# PAGE2.net
KiCad netlist of a schematic drawn in Altium Designer
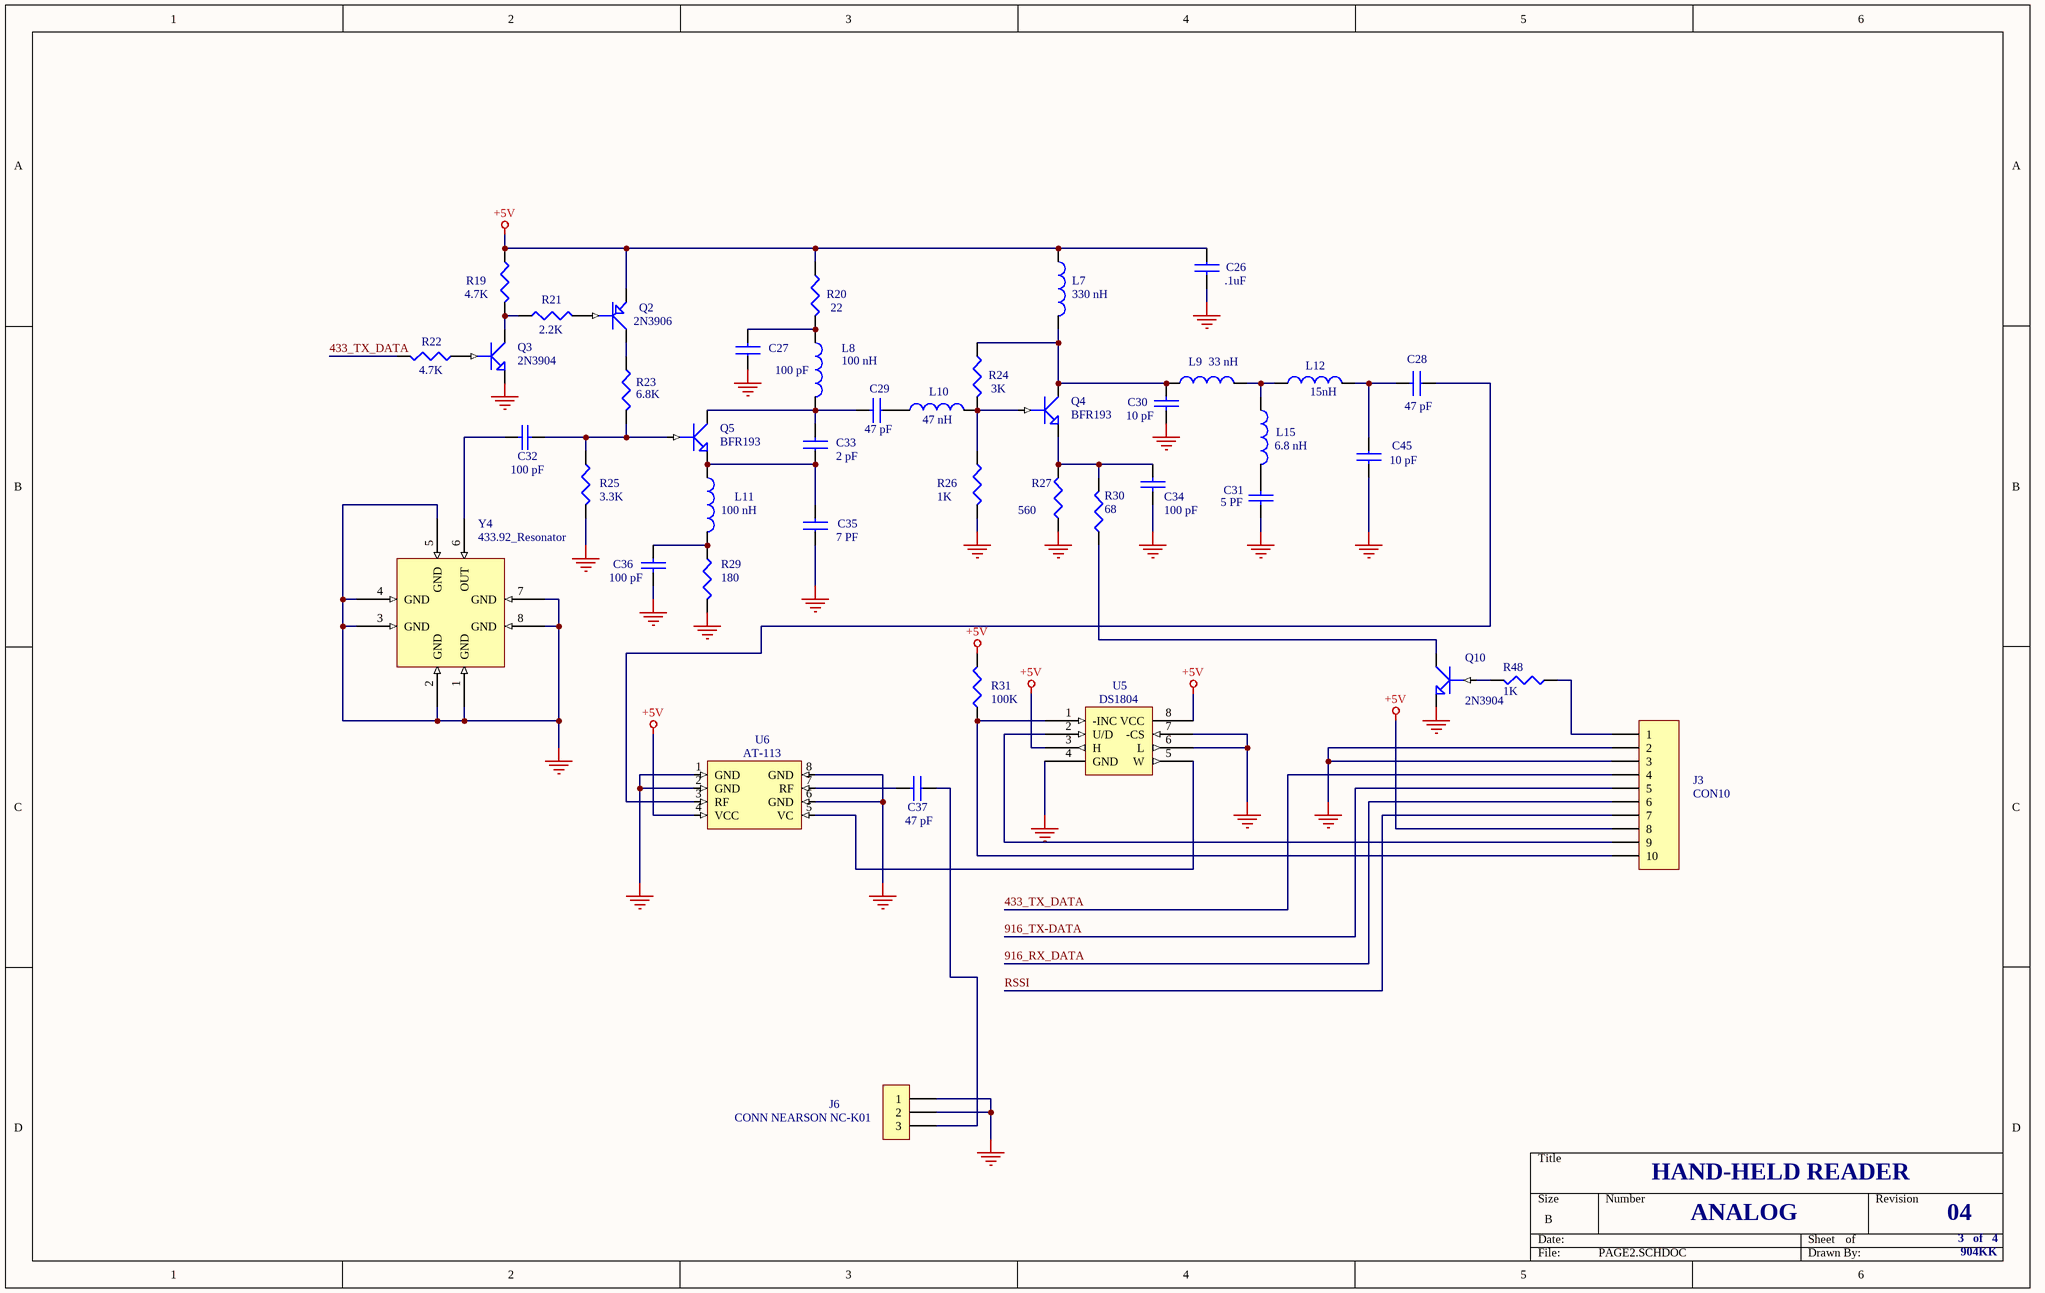
[diagram p0: PAGE2.SCHDOC]

(export (version "E")
  (design (tool "Eeschema 10.0.6"))
  (components
    (comp (ref "C26") (value ".1uF") (footprint "0603") (libsource (lib "*") (part "CAP_NP")))
    (comp (ref "C27") (value "100 pF") (footprint "0603") (libsource (lib "*") (part "CAP_NP")))
    (comp (ref "C28") (value "47 pF") (footprint "0603") (libsource (lib "*") (part "CAP_NP")))
    (comp (ref "C29") (value "47 pF") (footprint "0603") (libsource (lib "*") (part "CAP_NP")))
    (comp (ref "C30")
      (value "10 pF")
      (footprint "0603")
      (description "Capacitor")
      (libsource (lib "*") (part "CAP"))
    )
    (comp (ref "C31")
      (value "5 PF")
      (footprint "0603")
      (description "Capacitor")
      (libsource (lib "*") (part "CAP"))
    )
    (comp (ref "C32")
      (value "100 pF")
      (footprint "0603")
      (description "Capacitor")
      (libsource (lib "*") (part "CAP"))
    )
    (comp (ref "C33") (value "2 pF") (footprint "0603") (libsource (lib "*") (part "CAP_NP")))
    (comp (ref "C34")
      (value "100 pF")
      (footprint "0603")
      (description "Capacitor")
      (libsource (lib "*") (part "CAP"))
    )
    (comp (ref "C35") (value "7 PF") (footprint "0603") (libsource (lib "*") (part "CAP_NP")))
    (comp (ref "C36")
      (value "100 pF")
      (footprint "0603")
      (description "Capacitor")
      (libsource (lib "*") (part "CAP"))
    )
    (comp (ref "C37") (value "47 pF") (footprint "0603") (libsource (lib "*") (part "CAP_NP")))
    (comp (ref "C45") (value "10 pF") (footprint "0603") (libsource (lib "*") (part "CAP_NP")))
    (comp (ref "J3")
      (value "CON10")
      (footprint "1X10 HEADER SPECIAL")
      (description "Connector")
      (libsource (lib "*") (part "CON10"))
    )
    (comp (ref "J6")
      (value "CONN NEARSON NC-K01")
      (footprint "CONN NEARSON NC-K01")
      (description "Connector")
      (libsource (lib "*") (part "CON3"))
    )
    (comp (ref "L7") (value "330 nH") (footprint "0805") (libsource (lib "*") (part "INDUCTOR")))
    (comp (ref "L8") (value "100 nH") (footprint "0603") (libsource (lib "*") (part "INDUCTOR")))
    (comp (ref "L9") (value "33 nH") (footprint "0603") (libsource (lib "*") (part "INDUCTOR")))
    (comp (ref "L10") (value "47 nH") (footprint "0603") (libsource (lib "*") (part "INDUCTOR")))
    (comp (ref "L11") (value "100 nH") (footprint "0603") (libsource (lib "*") (part "INDUCTOR")))
    (comp (ref "L12") (value "15nH") (footprint "0603") (libsource (lib "*") (part "INDUCTOR")))
    (comp (ref "L15") (value "6.8 nH") (footprint "0603") (libsource (lib "*") (part "INDUCTOR")))
    (comp (ref "Q2")
      (value "2N3906")
      (footprint "SOT23 TRANS")
      (description "PNP Transistor")
      (libsource (lib "*") (part "PNP1"))
    )
    (comp (ref "Q3")
      (value "2N3904")
      (footprint "SOT23 TRANS")
      (description "NPN Transistor")
      (libsource (lib "*") (part "NPN1"))
    )
    (comp (ref "Q4")
      (value "BFR193")
      (footprint "SOT23 TRANS")
      (description "NPN Transistor")
      (libsource (lib "*") (part "NPN1"))
    )
    (comp (ref "Q5")
      (value "BFR193")
      (footprint "SOT23 TRANS")
      (description "NPN Transistor")
      (libsource (lib "*") (part "NPN1"))
    )
    (comp (ref "Q10")
      (value "2N3904")
      (footprint "SOT23 TRANS")
      (description "NPN Transistor")
      (libsource (lib "*") (part "NPN1"))
    )
    (comp (ref "R19") (value "4.7K") (footprint "0603") (libsource (lib "*") (part "RESISTOR")))
    (comp (ref "R20") (value "22") (footprint "0603") (libsource (lib "*") (part "RESISTOR")))
    (comp (ref "R21") (value "2.2K") (footprint "0603") (libsource (lib "*") (part "RESISTOR")))
    (comp (ref "R22") (value "4.7K") (footprint "0603") (libsource (lib "*") (part "RESISTOR")))
    (comp (ref "R23") (value "6.8K") (footprint "0603") (libsource (lib "*") (part "RESISTOR")))
    (comp (ref "R24") (value "3K") (footprint "0603") (libsource (lib "*") (part "RESISTOR")))
    (comp (ref "R25") (value "3.3K") (footprint "0603") (libsource (lib "*") (part "RESISTOR")))
    (comp (ref "R26") (value "1K") (footprint "0603") (libsource (lib "*") (part "RESISTOR")))
    (comp (ref "R27") (value "560") (footprint "0603") (libsource (lib "*") (part "RESISTOR")))
    (comp (ref "R29") (value "180") (footprint "0603") (libsource (lib "*") (part "RESISTOR")))
    (comp (ref "R30") (value "68") (footprint "0603") (libsource (lib "*") (part "RESISTOR")))
    (comp (ref "R31") (value "100K") (footprint "0603") (libsource (lib "*") (part "RESISTOR")))
    (comp (ref "R48") (value "1K") (footprint "0603") (libsource (lib "*") (part "RESISTOR")))
    (comp (ref "U5") (value "DS1804") (footprint "SO8 SMALL") (libsource (lib "*") (part "DS1804")))
    (comp (ref "U6") (value "AT-113") (footprint "SO8") (libsource (lib "*") (part "AT-113A")))
    (comp (ref "Y4")
      (value "433.92_Resonator")
      (footprint "RESONATOR")
      (libsource (lib "*") (part "RESONATOR"))
    )
  )
  (nets
    (net (code "1") (name "+5V") (class "Default")
      (node (ref "C26") (pin "1") (pinfunction "1_1") (pintype "passive"))
      (node (ref "J3") (pin "8") (pinfunction "8_8") (pintype "passive"))
      (node (ref "L7") (pin "1") (pinfunction "1_1") (pintype "passive"))
      (node (ref "Q2") (pin "E") (pinfunction "E_E") (pintype "passive"))
      (node (ref "R19") (pin "1") (pinfunction "1_1") (pintype "passive"))
      (node (ref "R20") (pin "1") (pinfunction "1_1") (pintype "passive"))
      (node (ref "R31") (pin "1") (pinfunction "1_1") (pintype "passive"))
      (node (ref "U5") (pin "3") (pinfunction "H_3") (pintype "output"))
      (node (ref "U5") (pin "8") (pinfunction "VCC_8") (pintype "power_in"))
      (node (ref "U6") (pin "4") (pinfunction "VCC_4") (pintype "input"))
    )
    (net (code "2") (name "/433_TX_DATA") (class "Default")
      (node (ref "J3") (pin "4") (pinfunction "4_4") (pintype "passive"))
      (node (ref "R22") (pin "2") (pinfunction "2_2") (pintype "passive"))
    )
    (net (code "3") (name "/916_RX_DATA") (class "Default")
      (node (ref "J3") (pin "6") (pinfunction "6_6") (pintype "passive"))
    )
    (net (code "4") (name "/916_TX-DATA") (class "Default")
      (node (ref "J3") (pin "5") (pinfunction "5_5") (pintype "passive"))
    )
    (net (code "5") (name "/RSSI") (class "Default")
      (node (ref "J3") (pin "7") (pinfunction "7_7") (pintype "passive"))
    )
    (net (code "6") (name "GND_SIGNAL") (class "Default")
      (node (ref "C26") (pin "2") (pinfunction "2_2") (pintype "passive"))
      (node (ref "C27") (pin "1") (pinfunction "1_1") (pintype "passive"))
      (node (ref "C30") (pin "2") (pinfunction "2_2") (pintype "passive"))
      (node (ref "C31") (pin "2") (pinfunction "2_2") (pintype "passive"))
      (node (ref "C34") (pin "2") (pinfunction "2_2") (pintype "passive"))
      (node (ref "C35") (pin "1") (pinfunction "1_1") (pintype "passive"))
      (node (ref "C36") (pin "2") (pinfunction "2_2") (pintype "passive"))
      (node (ref "C45") (pin "2") (pinfunction "2_2") (pintype "passive"))
      (node (ref "J3") (pin "2") (pinfunction "2_2") (pintype "passive"))
      (node (ref "J3") (pin "3") (pinfunction "3_3") (pintype "passive"))
      (node (ref "J6") (pin "1") (pinfunction "1_1") (pintype "passive"))
      (node (ref "J6") (pin "2") (pinfunction "2_2") (pintype "passive"))
      (node (ref "Q10") (pin "E") (pinfunction "E_E") (pintype "passive"))
      (node (ref "Q3") (pin "E") (pinfunction "E_E") (pintype "passive"))
      (node (ref "R25") (pin "2") (pinfunction "2_2") (pintype "passive"))
      (node (ref "R26") (pin "2") (pinfunction "2_2") (pintype "passive"))
      (node (ref "R27") (pin "2") (pinfunction "2_2") (pintype "passive"))
      (node (ref "R29") (pin "2") (pinfunction "2_2") (pintype "passive"))
      (node (ref "U5") (pin "4") (pinfunction "GND_4") (pintype "power_in"))
      (node (ref "U5") (pin "6") (pinfunction "L_6") (pintype "output"))
      (node (ref "U5") (pin "7") (pinfunction "-CS_7") (pintype "input"))
      (node (ref "U6") (pin "1") (pinfunction "GND_1") (pintype "input"))
      (node (ref "U6") (pin "2") (pinfunction "GND_2") (pintype "input"))
      (node (ref "U6") (pin "6") (pinfunction "GND_6") (pintype "input"))
      (node (ref "U6") (pin "8") (pinfunction "GND_8") (pintype "input"))
      (node (ref "Y4") (pin "1") (pinfunction "GND_1") (pintype "input"))
      (node (ref "Y4") (pin "2") (pinfunction "GND_2") (pintype "input"))
      (node (ref "Y4") (pin "3") (pinfunction "GND_3") (pintype "input"))
      (node (ref "Y4") (pin "4") (pinfunction "GND_4") (pintype "input"))
      (node (ref "Y4") (pin "5") (pinfunction "GND_5") (pintype "input"))
      (node (ref "Y4") (pin "7") (pinfunction "GND_7") (pintype "input"))
      (node (ref "Y4") (pin "8") (pinfunction "GND_8") (pintype "input"))
    )
    (net (code "7") (name "Net-(C27-Pad2)") (class "Default")
      (node (ref "C27") (pin "2") (pinfunction "2_2") (pintype "passive"))
      (node (ref "L8") (pin "1") (pinfunction "1_1") (pintype "passive"))
      (node (ref "R20") (pin "2") (pinfunction "2_2") (pintype "passive"))
    )
    (net (code "8") (name "Net-(C28-Pad1)") (class "Default")
      (node (ref "C28") (pin "1") (pinfunction "1_1") (pintype "passive"))
      (node (ref "U6") (pin "3") (pinfunction "RF_3") (pintype "input"))
    )
    (net (code "9") (name "Net-(C28-Pad2)") (class "Default")
      (node (ref "C28") (pin "2") (pinfunction "2_2") (pintype "passive"))
      (node (ref "C45") (pin "1") (pinfunction "1_1") (pintype "passive"))
      (node (ref "L12") (pin "2") (pinfunction "2_2") (pintype "passive"))
    )
    (net (code "10") (name "Net-(C29-Pad1)") (class "Default")
      (node (ref "C29") (pin "1") (pinfunction "1_1") (pintype "passive"))
      (node (ref "L10") (pin "1") (pinfunction "1_1") (pintype "passive"))
    )
    (net (code "11") (name "Net-(C29-Pad2)") (class "Default")
      (node (ref "C29") (pin "2") (pinfunction "2_2") (pintype "passive"))
      (node (ref "C33") (pin "2") (pinfunction "2_2") (pintype "passive"))
      (node (ref "L8") (pin "2") (pinfunction "2_2") (pintype "passive"))
      (node (ref "Q5") (pin "C") (pinfunction "C_C") (pintype "passive"))
    )
    (net (code "12") (name "Net-(C30-Pad1)") (class "Default")
      (node (ref "C30") (pin "1") (pinfunction "1_1") (pintype "passive"))
      (node (ref "L7") (pin "2") (pinfunction "2_2") (pintype "passive"))
      (node (ref "L9") (pin "1") (pinfunction "1_1") (pintype "passive"))
      (node (ref "Q4") (pin "C") (pinfunction "C_C") (pintype "passive"))
      (node (ref "R24") (pin "1") (pinfunction "1_1") (pintype "passive"))
    )
    (net (code "13") (name "Net-(C31-Pad1)") (class "Default")
      (node (ref "C31") (pin "1") (pinfunction "1_1") (pintype "passive"))
      (node (ref "L15") (pin "2") (pinfunction "2_2") (pintype "passive"))
    )
    (net (code "14") (name "Net-(C32-Pad2)") (class "Default")
      (node (ref "C32") (pin "2") (pinfunction "2_2") (pintype "passive"))
      (node (ref "Q5") (pin "B") (pinfunction "B_B") (pintype "input"))
      (node (ref "R23") (pin "2") (pinfunction "2_2") (pintype "passive"))
      (node (ref "R25") (pin "1") (pinfunction "1_1") (pintype "passive"))
    )
    (net (code "15") (name "Net-(C33-Pad1)") (class "Default")
      (node (ref "C33") (pin "1") (pinfunction "1_1") (pintype "passive"))
      (node (ref "C35") (pin "2") (pinfunction "2_2") (pintype "passive"))
      (node (ref "L11") (pin "1") (pinfunction "1_1") (pintype "passive"))
      (node (ref "Q5") (pin "E") (pinfunction "E_E") (pintype "passive"))
    )
    (net (code "16") (name "Net-(C34-Pad1)") (class "Default")
      (node (ref "C34") (pin "1") (pinfunction "1_1") (pintype "passive"))
      (node (ref "Q4") (pin "E") (pinfunction "E_E") (pintype "passive"))
      (node (ref "R27") (pin "1") (pinfunction "1_1") (pintype "passive"))
      (node (ref "R30") (pin "2") (pinfunction "2_2") (pintype "passive"))
    )
    (net (code "17") (name "Net-(C36-Pad1)") (class "Default")
      (node (ref "C36") (pin "1") (pinfunction "1_1") (pintype "passive"))
      (node (ref "L11") (pin "2") (pinfunction "2_2") (pintype "passive"))
      (node (ref "R29") (pin "1") (pinfunction "1_1") (pintype "passive"))
    )
    (net (code "18") (name "Net-(C37-Pad1)") (class "Default")
      (node (ref "C37") (pin "1") (pinfunction "1_1") (pintype "passive"))
      (node (ref "J6") (pin "3") (pinfunction "3_3") (pintype "passive"))
    )
    (net (code "19") (name "Net-(C37-Pad2)") (class "Default")
      (node (ref "C37") (pin "2") (pinfunction "2_2") (pintype "passive"))
      (node (ref "U6") (pin "7") (pinfunction "RF_7") (pintype "input"))
    )
    (net (code "20") (name "Net-(J3-Pad1)") (class "Default")
      (node (ref "J3") (pin "1") (pinfunction "1_1") (pintype "passive"))
      (node (ref "R48") (pin "2") (pinfunction "2_2") (pintype "passive"))
    )
    (net (code "21") (name "Net-(L10-Pad2)") (class "Default")
      (node (ref "L10") (pin "2") (pinfunction "2_2") (pintype "passive"))
      (node (ref "Q4") (pin "B") (pinfunction "B_B") (pintype "input"))
      (node (ref "R24") (pin "2") (pinfunction "2_2") (pintype "passive"))
      (node (ref "R26") (pin "1") (pinfunction "1_1") (pintype "passive"))
    )
    (net (code "22") (name "Net-(L12-Pad1)") (class "Default")
      (node (ref "L12") (pin "1") (pinfunction "1_1") (pintype "passive"))
      (node (ref "L15") (pin "1") (pinfunction "1_1") (pintype "passive"))
      (node (ref "L9") (pin "2") (pinfunction "2_2") (pintype "passive"))
    )
    (net (code "23") (name "Net-(Q2-PadB)") (class "Default")
      (node (ref "Q2") (pin "B") (pinfunction "B_B") (pintype "input"))
      (node (ref "R21") (pin "2") (pinfunction "2_2") (pintype "passive"))
    )
    (net (code "24") (name "Net-(Q2-PadC)") (class "Default")
      (node (ref "Q2") (pin "C") (pinfunction "C_C") (pintype "passive"))
      (node (ref "R23") (pin "1") (pinfunction "1_1") (pintype "passive"))
    )
    (net (code "25") (name "Net-(Q3-PadB)") (class "Default")
      (node (ref "Q3") (pin "B") (pinfunction "B_B") (pintype "input"))
      (node (ref "R22") (pin "1") (pinfunction "1_1") (pintype "passive"))
    )
    (net (code "26") (name "Net-(Q3-PadC)") (class "Default")
      (node (ref "Q3") (pin "C") (pinfunction "C_C") (pintype "passive"))
      (node (ref "R19") (pin "2") (pinfunction "2_2") (pintype "passive"))
      (node (ref "R21") (pin "1") (pinfunction "1_1") (pintype "passive"))
    )
    (net (code "27") (name "Net-(Q10-PadB)") (class "Default")
      (node (ref "Q10") (pin "B") (pinfunction "B_B") (pintype "input"))
      (node (ref "R48") (pin "1") (pinfunction "1_1") (pintype "passive"))
    )
    (net (code "28") (name "Net-(Q10-PadC)") (class "Default")
      (node (ref "Q10") (pin "C") (pinfunction "C_C") (pintype "passive"))
      (node (ref "R30") (pin "1") (pinfunction "1_1") (pintype "passive"))
    )
    (net (code "29") (name "Net-(U5--INC)") (class "Default")
      (node (ref "J3") (pin "10") (pinfunction "10_10") (pintype "passive"))
      (node (ref "R31") (pin "2") (pinfunction "2_2") (pintype "passive"))
      (node (ref "U5") (pin "1") (pinfunction "-INC_1") (pintype "input"))
    )
    (net (code "30") (name "Net-(U5-U{slash}D)") (class "Default")
      (node (ref "J3") (pin "9") (pinfunction "9_9") (pintype "passive"))
      (node (ref "U5") (pin "2") (pinfunction "U/D_2") (pintype "input"))
    )
    (net (code "31") (name "Net-(U5-W)") (class "Default")
      (node (ref "U5") (pin "5") (pinfunction "W_5") (pintype "output"))
      (node (ref "U6") (pin "5") (pinfunction "VC_5") (pintype "input"))
    )
    (net (code "32") (name "Net-(Y4-OUT)") (class "Default")
      (node (ref "C32") (pin "1") (pinfunction "1_1") (pintype "passive"))
      (node (ref "Y4") (pin "6") (pinfunction "OUT_6") (pintype "input"))
    )
  )
)
